# VelocistaEdu_soloshield.net
KiCad netlist of a schematic drawn in EAGLE
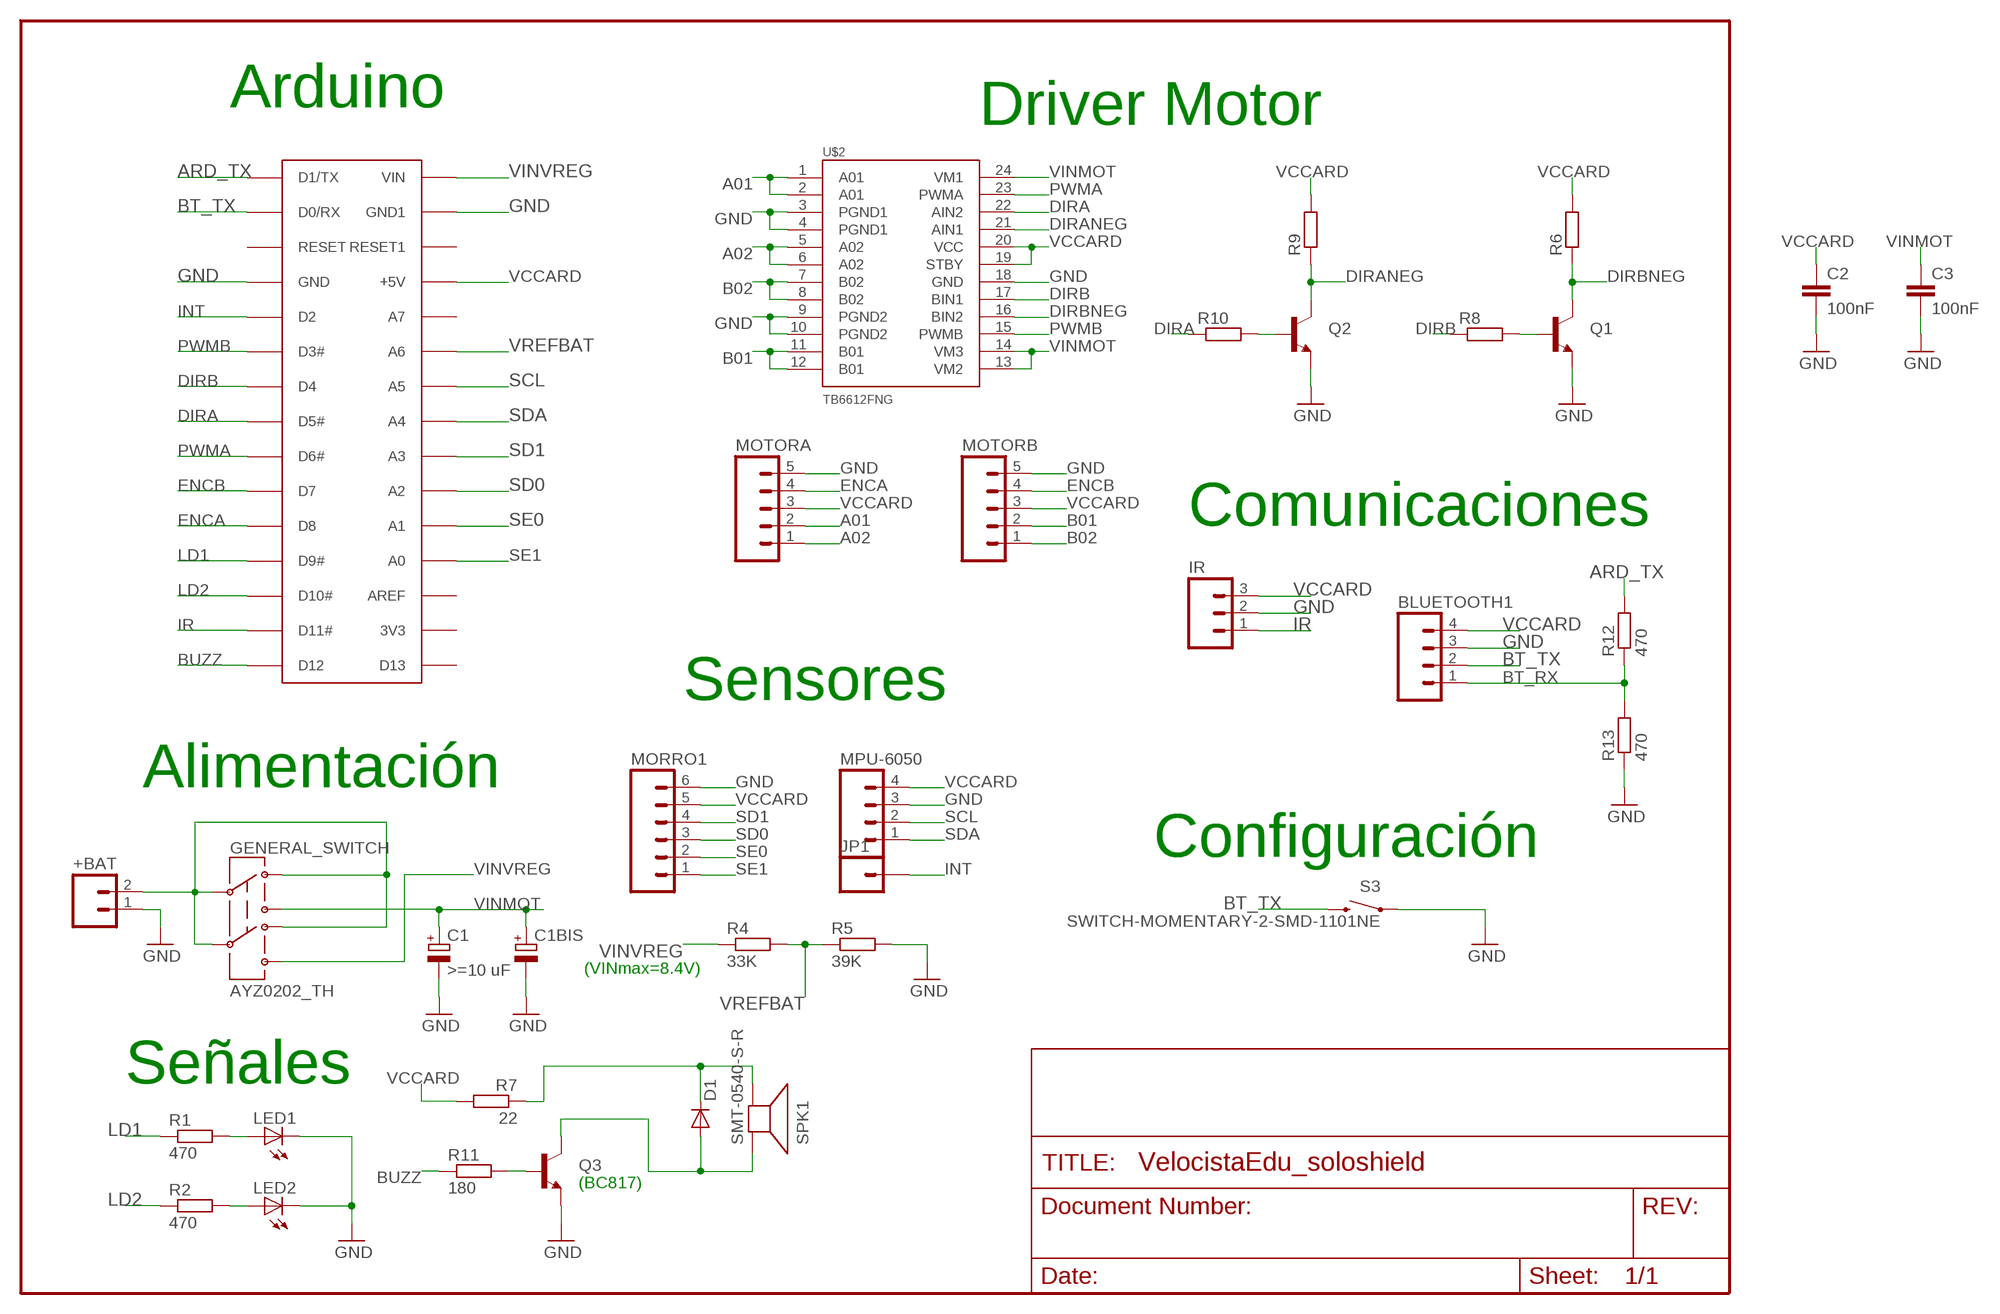
[diagram p0: schematic, sheet 1]

(export (version "E")
  (design (tool "Eeschema 10.0.6"))
  (components
    (comp (ref "+BAT")
      (value "M02LOCK_LONGPADS")
      (footprint "eagle-import:1X02_LOCK_LONGPADS")
      (libsource (lib "eagle-import") (part "M02LOCK_LONGPADS"))
    )
    (comp (ref "BLUETOOTH1")
      (value "M04LONGPADS")
      (footprint "eagle-import:1X04_LONGPADS")
      (libsource (lib "eagle-import") (part "M04LONGPADS"))
    )
    (comp (ref "C1")
      (value ">=10 uF")
      (footprint "eagle-import:SMC_C")
      (libsource (lib "eagle-import") (part "CPOL-EUSMCC"))
    )
    (comp (ref "C1BIS")
      (value "CPOL-EUE2.5-5")
      (footprint "eagle-import:E2,5-5")
      (libsource (lib "eagle-import") (part "CPOL-EUE2.5-5"))
    )
    (comp (ref "C2")
      (value "100nF")
      (footprint "eagle-import:C0805")
      (libsource (lib "eagle-import") (part "C-EUC0805"))
    )
    (comp (ref "C3")
      (value "100nF")
      (footprint "eagle-import:C0805")
      (libsource (lib "eagle-import") (part "C-EUC0805"))
    )
    (comp (ref "D1")
      (value "DIODE-MICROMELF-W")
      (footprint "eagle-import:MICROMELF-W")
      (libsource (lib "eagle-import") (part "DIODE-MICROMELF-W"))
    )
    (comp (ref "GENERAL_SWITCH")
      (value "AYZ0202_TH")
      (footprint "eagle-import:AYZ0202_TH")
      (libsource (lib "eagle-import") (part "AYZ0202_TH"))
    )
    (comp (ref "IR")
      (value "M03LONGPADS")
      (footprint "eagle-import:1X03_LONGPADS")
      (libsource (lib "eagle-import") (part "M03LONGPADS"))
    )
    (comp (ref "JP1")
      (value "M01PTH_LONGPAD")
      (footprint "eagle-import:1X01_LONGPAD")
      (libsource (lib "eagle-import") (part "M01PTH_LONGPAD"))
    )
    (comp (ref "LED1")
      (value "LEDCHIPLED_0805")
      (footprint "eagle-import:CHIPLED_0805")
      (libsource (lib "eagle-import") (part "LEDCHIPLED_0805"))
    )
    (comp (ref "LED2")
      (value "LEDCHIPLED_0805")
      (footprint "eagle-import:CHIPLED_0805")
      (libsource (lib "eagle-import") (part "LEDCHIPLED_0805"))
    )
    (comp (ref "MORRO1")
      (value "M06LONGPADS")
      (footprint "eagle-import:1X06_LONGPADS")
      (libsource (lib "eagle-import") (part "M06LONGPADS"))
    )
    (comp (ref "MOTORA")
      (value "M05PTH")
      (footprint "eagle-import:1X05")
      (libsource (lib "eagle-import") (part "M05PTH"))
    )
    (comp (ref "MOTORB")
      (value "M05PTH")
      (footprint "eagle-import:1X05")
      (libsource (lib "eagle-import") (part "M05PTH"))
    )
    (comp (ref "MPU-6050")
      (value "M04LONGPADS")
      (footprint "eagle-import:1X04_LONGPADS")
      (libsource (lib "eagle-import") (part "M04LONGPADS"))
    )
    (comp (ref "Q1")
      (value "TRANSISTOR_NPNSOT23")
      (footprint "eagle-import:SOT23")
      (libsource (lib "eagle-import") (part "TRANSISTOR_NPNSOT23"))
    )
    (comp (ref "Q2")
      (value "TRANSISTOR_NPNSOT23")
      (footprint "eagle-import:SOT23")
      (libsource (lib "eagle-import") (part "TRANSISTOR_NPNSOT23"))
    )
    (comp (ref "Q3")
      (value "TRANSISTOR_NPNSOT23")
      (footprint "eagle-import:SOT23")
      (libsource (lib "eagle-import") (part "TRANSISTOR_NPNSOT23"))
    )
    (comp (ref "R1")
      (value "470")
      (footprint "eagle-import:R0805")
      (libsource (lib "eagle-import") (part "resistor_R-EU_R0805"))
    )
    (comp (ref "R2")
      (value "470")
      (footprint "eagle-import:R0805")
      (libsource (lib "eagle-import") (part "resistor_R-EU_R0805"))
    )
    (comp (ref "R4")
      (value "33K")
      (footprint "eagle-import:R0805")
      (libsource (lib "eagle-import") (part "resistor_R-EU_R0805"))
    )
    (comp (ref "R5")
      (value "39K")
      (footprint "eagle-import:R0805")
      (libsource (lib "eagle-import") (part "resistor_R-EU_R0805"))
    )
    (comp (ref "R6")
      (value "R-EU_M0805")
      (footprint "eagle-import:M0805")
      (libsource (lib "eagle-import") (part "R-EU_M0805"))
    )
    (comp (ref "R7")
      (value "22")
      (footprint "eagle-import:R0805")
      (libsource (lib "eagle-import") (part "resistor_R-EU_R0805"))
    )
    (comp (ref "R8")
      (value "R-EU_M0805")
      (footprint "eagle-import:M0805")
      (libsource (lib "eagle-import") (part "R-EU_M0805"))
    )
    (comp (ref "R9")
      (value "R-EU_M0805")
      (footprint "eagle-import:M0805")
      (libsource (lib "eagle-import") (part "R-EU_M0805"))
    )
    (comp (ref "R10")
      (value "R-EU_M0805")
      (footprint "eagle-import:M0805")
      (libsource (lib "eagle-import") (part "R-EU_M0805"))
    )
    (comp (ref "R11")
      (value "180")
      (footprint "eagle-import:M0805")
      (libsource (lib "eagle-import") (part "R-EU_M0805"))
    )
    (comp (ref "R12")
      (value "470")
      (footprint "eagle-import:R0805")
      (libsource (lib "eagle-import") (part "resistor_R-EU_R0805"))
    )
    (comp (ref "R13")
      (value "470")
      (footprint "eagle-import:R0805")
      (libsource (lib "eagle-import") (part "resistor_R-EU_R0805"))
    )
    (comp (ref "S3")
      (value "SWITCH-MOMENTARY-2-SMD-1101NE")
      (footprint "eagle-import:TACTILE-SWITCH-1101NE")
      (libsource (lib "eagle-import") (part "SWITCH-MOMENTARY-2-SMD-1101NE"))
    )
    (comp (ref "SPK1")
      (value "SMT-0540-S-R")
      (footprint "eagle-import:SMT-0540-S-R")
      (libsource (lib "eagle-import") (part "SMT-0540-S-R"))
    )
    (comp (ref "U$1")
      (value "ARDUINONANONOHOLES")
      (footprint "eagle-import:PDIP-32NOHOLES")
      (libsource (lib "eagle-import") (part "ARDUINONANONOHOLES"))
    )
    (comp (ref "U$2")
      (value "TB6612FNG")
      (footprint "eagle-import:SSOP24")
      (libsource (lib "eagle-import") (part "TB6612FNG"))
    )
  )
  (nets
    (net (code "1") (name "/A01") (class "Default")
      (node (ref "MOTORA") (pin "2") (pinfunction "2_2") (pintype "passive"))
      (node (ref "U$2") (pin "1") (pinfunction "A01_1") (pintype "bidirectional"))
      (node (ref "U$2") (pin "2") (pinfunction "A01_2") (pintype "bidirectional"))
    )
    (net (code "2") (name "/A02") (class "Default")
      (node (ref "MOTORA") (pin "1") (pinfunction "1_1") (pintype "passive"))
      (node (ref "U$2") (pin "5") (pinfunction "A02_5") (pintype "bidirectional"))
      (node (ref "U$2") (pin "6") (pinfunction "A02_6") (pintype "bidirectional"))
    )
    (net (code "3") (name "/ARD_TX") (class "Default")
      (node (ref "R12") (pin "2") (pinfunction "2_2") (pintype "passive"))
      (node (ref "U$1") (pin "D1/TX") (pinfunction "D1/TX_D1/TX") (pintype "bidirectional"))
    )
    (net (code "4") (name "/B01") (class "Default")
      (node (ref "MOTORB") (pin "2") (pinfunction "2_2") (pintype "passive"))
      (node (ref "U$2") (pin "11") (pinfunction "B01_11") (pintype "bidirectional"))
      (node (ref "U$2") (pin "12") (pinfunction "B01_12") (pintype "bidirectional"))
    )
    (net (code "5") (name "/B02") (class "Default")
      (node (ref "MOTORB") (pin "1") (pinfunction "1_1") (pintype "passive"))
      (node (ref "U$2") (pin "7") (pinfunction "B02_7") (pintype "bidirectional"))
      (node (ref "U$2") (pin "8") (pinfunction "B02_8") (pintype "bidirectional"))
    )
    (net (code "6") (name "/BT_RX") (class "Default")
      (node (ref "BLUETOOTH1") (pin "1") (pinfunction "1_1") (pintype "passive"))
      (node (ref "R12") (pin "1") (pinfunction "1_1") (pintype "passive"))
      (node (ref "R13") (pin "2") (pinfunction "2_2") (pintype "passive"))
    )
    (net (code "7") (name "/BT_TX") (class "Default")
      (node (ref "BLUETOOTH1") (pin "2") (pinfunction "2_2") (pintype "passive"))
      (node (ref "S3") (pin "P$2") (pinfunction "2_P$2") (pintype "passive"))
      (node (ref "U$1") (pin "D0/RX") (pinfunction "D0/RX_D0/RX") (pintype "bidirectional"))
    )
    (net (code "8") (name "/BUZZ") (class "Default")
      (node (ref "R11") (pin "1") (pinfunction "1_1") (pintype "passive"))
      (node (ref "U$1") (pin "D12") (pinfunction "D12_D12") (pintype "bidirectional"))
    )
    (net (code "9") (name "/DIRA") (class "Default")
      (node (ref "R10") (pin "1") (pinfunction "1_1") (pintype "passive"))
      (node (ref "U$1") (pin "D5") (pinfunction "D5#_D5") (pintype "bidirectional"))
      (node (ref "U$2") (pin "22") (pinfunction "AIN2_22") (pintype "bidirectional"))
    )
    (net (code "10") (name "/DIRANEG") (class "Default")
      (node (ref "Q2") (pin "3") (pinfunction "C_3") (pintype "passive"))
      (node (ref "R9") (pin "1") (pinfunction "1_1") (pintype "passive"))
      (node (ref "U$2") (pin "21") (pinfunction "AIN1_21") (pintype "bidirectional"))
    )
    (net (code "11") (name "/DIRB") (class "Default")
      (node (ref "R8") (pin "1") (pinfunction "1_1") (pintype "passive"))
      (node (ref "U$1") (pin "D4") (pinfunction "D4_D4") (pintype "bidirectional"))
      (node (ref "U$2") (pin "17") (pinfunction "BIN1_17") (pintype "bidirectional"))
    )
    (net (code "12") (name "/DIRBNEG") (class "Default")
      (node (ref "Q1") (pin "3") (pinfunction "C_3") (pintype "passive"))
      (node (ref "R6") (pin "1") (pinfunction "1_1") (pintype "passive"))
      (node (ref "U$2") (pin "16") (pinfunction "BIN2_16") (pintype "bidirectional"))
    )
    (net (code "13") (name "/ENCA") (class "Default")
      (node (ref "MOTORA") (pin "4") (pinfunction "4_4") (pintype "passive"))
      (node (ref "U$1") (pin "D8") (pinfunction "D8_D8") (pintype "bidirectional"))
    )
    (net (code "14") (name "/ENCB") (class "Default")
      (node (ref "MOTORB") (pin "4") (pinfunction "4_4") (pintype "passive"))
      (node (ref "U$1") (pin "D7") (pinfunction "D7_D7") (pintype "bidirectional"))
    )
    (net (code "15") (name "/INT") (class "Default")
      (node (ref "JP1") (pin "1") (pinfunction "1_1") (pintype "passive"))
      (node (ref "U$1") (pin "D2") (pinfunction "D2_D2") (pintype "bidirectional"))
    )
    (net (code "16") (name "/IR") (class "Default")
      (node (ref "IR") (pin "1") (pinfunction "1_1") (pintype "passive"))
      (node (ref "U$1") (pin "D11") (pinfunction "D11#_D11") (pintype "bidirectional"))
    )
    (net (code "17") (name "/LD1") (class "Default")
      (node (ref "R1") (pin "1") (pinfunction "1_1") (pintype "passive"))
      (node (ref "U$1") (pin "D9") (pinfunction "D9#_D9") (pintype "bidirectional"))
    )
    (net (code "18") (name "/LD2") (class "Default")
      (node (ref "R2") (pin "1") (pinfunction "1_1") (pintype "passive"))
      (node (ref "U$1") (pin "D10") (pinfunction "D10#_D10") (pintype "bidirectional"))
    )
    (net (code "19") (name "/PWMA") (class "Default")
      (node (ref "U$1") (pin "D6") (pinfunction "D6#_D6") (pintype "bidirectional"))
      (node (ref "U$2") (pin "23") (pinfunction "PWMA_23") (pintype "bidirectional"))
    )
    (net (code "20") (name "/PWMB") (class "Default")
      (node (ref "U$1") (pin "D3") (pinfunction "D3#_D3") (pintype "bidirectional"))
      (node (ref "U$2") (pin "15") (pinfunction "PWMB_15") (pintype "bidirectional"))
    )
    (net (code "21") (name "/SCL") (class "Default")
      (node (ref "MPU-6050") (pin "2") (pinfunction "2_2") (pintype "passive"))
      (node (ref "U$1") (pin "A5") (pinfunction "A5_A5") (pintype "bidirectional"))
    )
    (net (code "22") (name "/SD0") (class "Default")
      (node (ref "MORRO1") (pin "3") (pinfunction "3_3") (pintype "passive"))
      (node (ref "U$1") (pin "A2") (pinfunction "A2_A2") (pintype "bidirectional"))
    )
    (net (code "23") (name "/SD1") (class "Default")
      (node (ref "MORRO1") (pin "4") (pinfunction "4_4") (pintype "passive"))
      (node (ref "U$1") (pin "A3") (pinfunction "A3_A3") (pintype "bidirectional"))
    )
    (net (code "24") (name "/SDA") (class "Default")
      (node (ref "MPU-6050") (pin "1") (pinfunction "1_1") (pintype "passive"))
      (node (ref "U$1") (pin "A4") (pinfunction "A4_A4") (pintype "bidirectional"))
    )
    (net (code "25") (name "/SE0") (class "Default")
      (node (ref "MORRO1") (pin "2") (pinfunction "2_2") (pintype "passive"))
      (node (ref "U$1") (pin "A1") (pinfunction "A1_A1") (pintype "bidirectional"))
    )
    (net (code "26") (name "/SE1") (class "Default")
      (node (ref "MORRO1") (pin "1") (pinfunction "1_1") (pintype "passive"))
      (node (ref "U$1") (pin "A0") (pinfunction "A0_A0") (pintype "bidirectional"))
    )
    (net (code "27") (name "/VCCARD") (class "Default")
      (node (ref "BLUETOOTH1") (pin "4") (pinfunction "4_4") (pintype "passive"))
      (node (ref "C2") (pin "1") (pinfunction "1_1") (pintype "passive"))
      (node (ref "IR") (pin "3") (pinfunction "3_3") (pintype "passive"))
      (node (ref "MORRO1") (pin "5") (pinfunction "5_5") (pintype "passive"))
      (node (ref "MOTORA") (pin "3") (pinfunction "3_3") (pintype "passive"))
      (node (ref "MOTORB") (pin "3") (pinfunction "3_3") (pintype "passive"))
      (node (ref "MPU-6050") (pin "4") (pinfunction "4_4") (pintype "passive"))
      (node (ref "R6") (pin "2") (pinfunction "2_2") (pintype "passive"))
      (node (ref "R7") (pin "2") (pinfunction "2_2") (pintype "passive"))
      (node (ref "R9") (pin "2") (pinfunction "2_2") (pintype "passive"))
      (node (ref "U$1") (pin "+5V") (pinfunction "+5V_+5V") (pintype "bidirectional"))
      (node (ref "U$2") (pin "19") (pinfunction "STBY_19") (pintype "bidirectional"))
      (node (ref "U$2") (pin "20") (pinfunction "VCC_20") (pintype "bidirectional"))
    )
    (net (code "28") (name "/VINMOT") (class "Default")
      (node (ref "C1") (pin "+") (pinfunction "+_+") (pintype "passive"))
      (node (ref "C1BIS") (pin "+") (pinfunction "+_+") (pintype "passive"))
      (node (ref "C3") (pin "1") (pinfunction "1_1") (pintype "passive"))
      (node (ref "GENERAL_SWITCH") (pin "B1") (pinfunction "B1_B1") (pintype "bidirectional"))
      (node (ref "U$2") (pin "13") (pinfunction "VM2_13") (pintype "bidirectional"))
      (node (ref "U$2") (pin "14") (pinfunction "VM3_14") (pintype "bidirectional"))
      (node (ref "U$2") (pin "24") (pinfunction "VM1_24") (pintype "bidirectional"))
    )
    (net (code "29") (name "/VINVREG") (class "Default")
      (node (ref "GENERAL_SWITCH") (pin "B2") (pinfunction "B2_B2") (pintype "bidirectional"))
      (node (ref "R4") (pin "1") (pinfunction "1_1") (pintype "passive"))
      (node (ref "U$1") (pin "VIN") (pinfunction "VIN_VIN") (pintype "bidirectional"))
    )
    (net (code "30") (name "/VREFBAT") (class "Default")
      (node (ref "R4") (pin "2") (pinfunction "2_2") (pintype "passive"))
      (node (ref "R5") (pin "1") (pinfunction "1_1") (pintype "passive"))
      (node (ref "U$1") (pin "A6") (pinfunction "A6_A6") (pintype "bidirectional"))
    )
    (net (code "31") (name "GND") (class "Default")
      (node (ref "+BAT") (pin "1") (pinfunction "1_1") (pintype "passive"))
      (node (ref "BLUETOOTH1") (pin "3") (pinfunction "3_3") (pintype "passive"))
      (node (ref "C1") (pin "-") (pinfunction "-_-") (pintype "passive"))
      (node (ref "C1BIS") (pin "-") (pinfunction "-_-") (pintype "passive"))
      (node (ref "C2") (pin "2") (pinfunction "2_2") (pintype "passive"))
      (node (ref "C3") (pin "2") (pinfunction "2_2") (pintype "passive"))
      (node (ref "IR") (pin "2") (pinfunction "2_2") (pintype "passive"))
      (node (ref "LED1") (pin "C") (pinfunction "C_C") (pintype "passive"))
      (node (ref "LED2") (pin "C") (pinfunction "C_C") (pintype "passive"))
      (node (ref "MORRO1") (pin "6") (pinfunction "6_6") (pintype "passive"))
      (node (ref "MOTORA") (pin "5") (pinfunction "5_5") (pintype "passive"))
      (node (ref "MOTORB") (pin "5") (pinfunction "5_5") (pintype "passive"))
      (node (ref "MPU-6050") (pin "3") (pinfunction "3_3") (pintype "passive"))
      (node (ref "Q1") (pin "2") (pinfunction "E_2") (pintype "passive"))
      (node (ref "Q2") (pin "2") (pinfunction "E_2") (pintype "passive"))
      (node (ref "Q3") (pin "2") (pinfunction "E_2") (pintype "passive"))
      (node (ref "R13") (pin "1") (pinfunction "1_1") (pintype "passive"))
      (node (ref "R5") (pin "2") (pinfunction "2_2") (pintype "passive"))
      (node (ref "S3") (pin "P$1") (pinfunction "1_P$1") (pintype "passive"))
      (node (ref "U$1") (pin "GND") (pinfunction "GND_GND") (pintype "bidirectional"))
      (node (ref "U$1") (pin "GND1") (pinfunction "GND1_GND1") (pintype "bidirectional"))
      (node (ref "U$2") (pin "10") (pinfunction "PGND2_10") (pintype "bidirectional"))
      (node (ref "U$2") (pin "18") (pinfunction "GND_18") (pintype "bidirectional"))
      (node (ref "U$2") (pin "3") (pinfunction "PGND1_3") (pintype "bidirectional"))
      (node (ref "U$2") (pin "4") (pinfunction "PGND1_4") (pintype "bidirectional"))
      (node (ref "U$2") (pin "9") (pinfunction "PGND2_9") (pintype "bidirectional"))
    )
    (net (code "32") (name "Net-(+BAT-Pad2)") (class "Default")
      (node (ref "+BAT") (pin "2") (pinfunction "2_2") (pintype "passive"))
      (node (ref "GENERAL_SWITCH") (pin "C1") (pinfunction "C1_C1") (pintype "bidirectional"))
      (node (ref "GENERAL_SWITCH") (pin "C2") (pinfunction "C2_C2") (pintype "bidirectional"))
      (node (ref "GENERAL_SWITCH") (pin "D1") (pinfunction "D1_D1") (pintype "bidirectional"))
      (node (ref "GENERAL_SWITCH") (pin "D2") (pinfunction "D2_D2") (pintype "bidirectional"))
    )
    (net (code "33") (name "Net-(LED1-PadA)") (class "Default")
      (node (ref "LED1") (pin "A") (pinfunction "A_A") (pintype "passive"))
      (node (ref "R1") (pin "2") (pinfunction "2_2") (pintype "passive"))
    )
    (net (code "34") (name "Net-(LED2-PadA)") (class "Default")
      (node (ref "LED2") (pin "A") (pinfunction "A_A") (pintype "passive"))
      (node (ref "R2") (pin "2") (pinfunction "2_2") (pintype "passive"))
    )
    (net (code "35") (name "Net-(Q1-B)") (class "Default")
      (node (ref "Q1") (pin "1") (pinfunction "B_1") (pintype "passive"))
      (node (ref "R8") (pin "2") (pinfunction "2_2") (pintype "passive"))
    )
    (net (code "36") (name "Net-(Q2-B)") (class "Default")
      (node (ref "Q2") (pin "1") (pinfunction "B_1") (pintype "passive"))
      (node (ref "R10") (pin "2") (pinfunction "2_2") (pintype "passive"))
    )
    (net (code "37") (name "Net-(Q3-B)") (class "Default")
      (node (ref "Q3") (pin "1") (pinfunction "B_1") (pintype "passive"))
      (node (ref "R11") (pin "2") (pinfunction "2_2") (pintype "passive"))
    )
    (net (code "38") (name "Net-(Q3-C)") (class "Default")
      (node (ref "D1") (pin "A") (pinfunction "A_A") (pintype "passive"))
      (node (ref "Q3") (pin "3") (pinfunction "C_3") (pintype "passive"))
      (node (ref "SPK1") (pin "-") (pinfunction "+_-") (pintype "passive"))
    )
    (net (code "39") (name "Net-(SPK1--)") (class "Default")
      (node (ref "D1") (pin "C") (pinfunction "C_C") (pintype "passive"))
      (node (ref "R7") (pin "1") (pinfunction "1_1") (pintype "passive"))
      (node (ref "SPK1") (pin "+") (pinfunction "-_+") (pintype "passive"))
    )
    (net (code "40") (name "unconnected-(U$1-Pad3V3)") (class "Default")
      (node (ref "U$1") (pin "3V3") (pinfunction "3V3_3V3") (pintype "bidirectional"))
    )
    (net (code "41") (name "unconnected-(U$1-PadA7)") (class "Default")
      (node (ref "U$1") (pin "A7") (pinfunction "A7_A7") (pintype "bidirectional"))
    )
    (net (code "42") (name "unconnected-(U$1-PadAREF)") (class "Default")
      (node (ref "U$1") (pin "AREF") (pinfunction "AREF_AREF") (pintype "bidirectional"))
    )
    (net (code "43") (name "unconnected-(U$1-PadD13)") (class "Default")
      (node (ref "U$1") (pin "D13") (pinfunction "D13_D13") (pintype "bidirectional"))
    )
    (net (code "44") (name "unconnected-(U$1-PadRESET)") (class "Default")
      (node (ref "U$1") (pin "RESET") (pinfunction "RESET_RESET") (pintype "bidirectional"))
    )
    (net (code "45") (name "unconnected-(U$1-PadRESET1)") (class "Default")
      (node (ref "U$1") (pin "RESET1") (pinfunction "RESET1_RESET1") (pintype "bidirectional"))
    )
  )
)
